# MCU_DAQ.net
KiCad netlist of a schematic drawn in Altium Designer
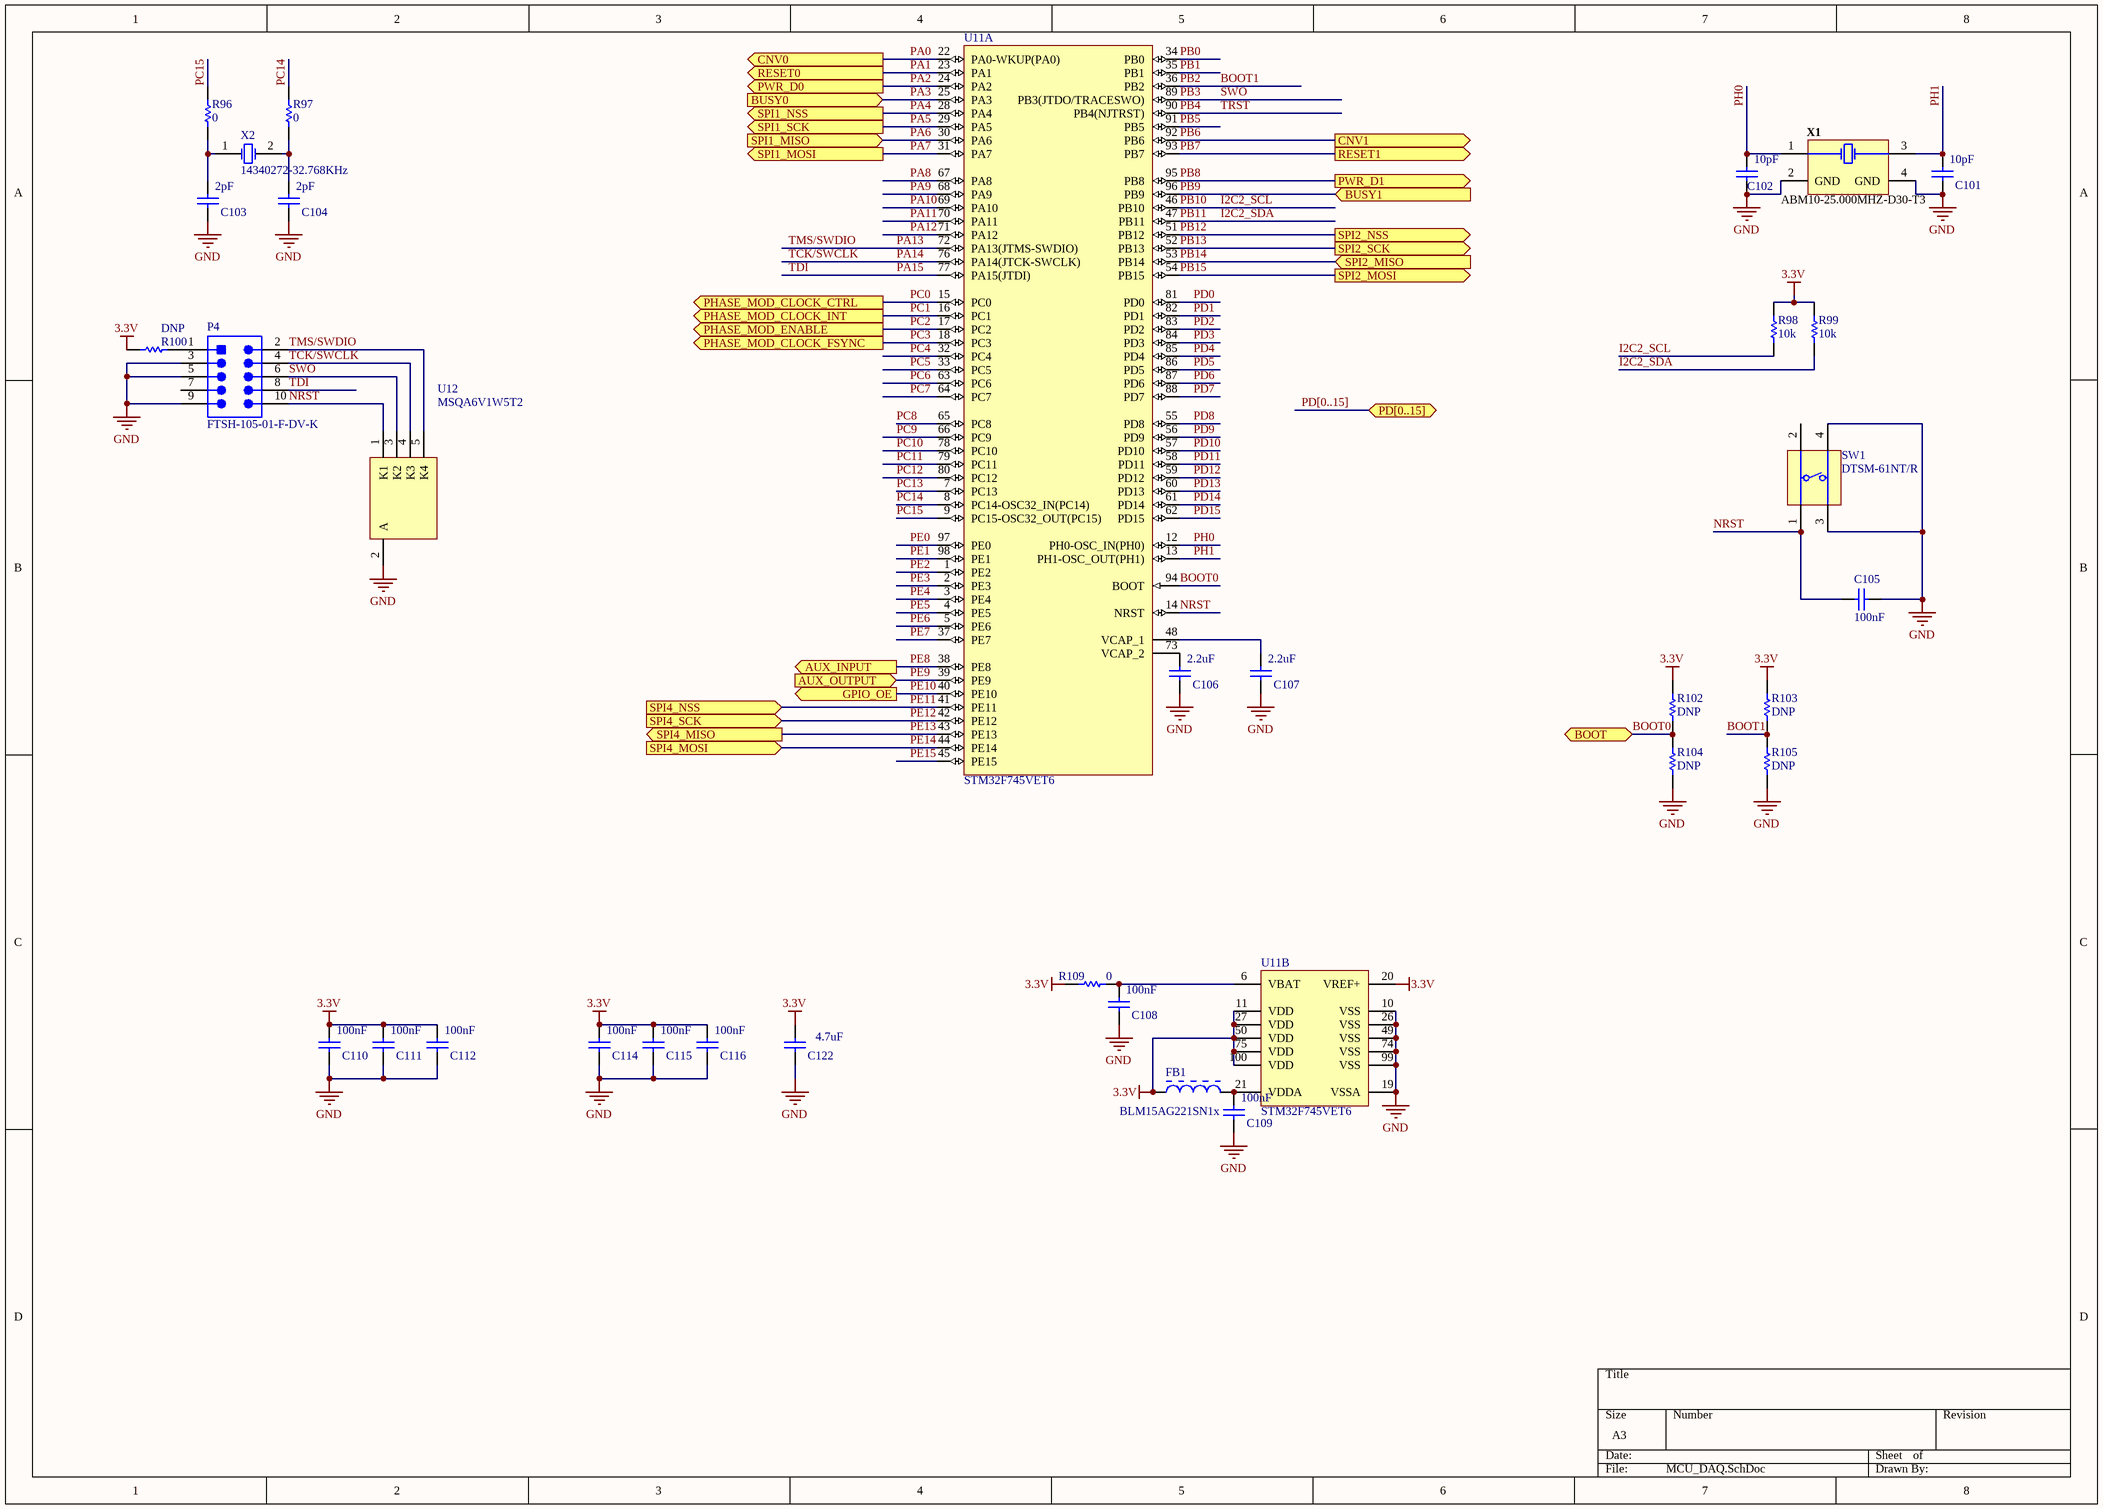
[diagram p0: MCU_DAQ.SchDoc]

(export (version "E")
  (design (tool "Eeschema 10.0.6"))
  (components
    (comp (ref "C101")
      (value "10pF")
      (footprint "CAPC0402(1005)60_L")
      (description "0402 (1005 Metric) Chip Capacitor")
      (fields (field (name "Comment") "CAP0402"))
      (libsource (lib "Altium Content Vault") (part "CMP-1590-00004-1"))
    )
    (comp (ref "C102")
      (value "10pF")
      (footprint "CAPC0402(1005)60_L")
      (description "0402 (1005 Metric) Chip Capacitor")
      (fields (field (name "Comment") "CAP0402"))
      (libsource (lib "Altium Content Vault") (part "CMP-1590-00004-1"))
    )
    (comp (ref "C103")
      (value "2pF")
      (footprint "CAPC0402(1005)60_L")
      (description "0402 (1005 Metric) Chip Capacitor")
      (fields (field (name "Comment") "CAP0402"))
      (libsource (lib "Altium Content Vault") (part "CMP-1590-00004-1"))
    )
    (comp (ref "C104")
      (value "2pF")
      (footprint "CAPC0402(1005)60_L")
      (description "0402 (1005 Metric) Chip Capacitor")
      (fields (field (name "Comment") "CAP0402"))
      (libsource (lib "Altium Content Vault") (part "CMP-1590-00004-1"))
    )
    (comp (ref "C105")
      (value "100nF")
      (footprint "CAPC0402(1005)60_L")
      (description "0402 (1005 Metric) Chip Capacitor")
      (fields (field (name "Comment") "CAP0402"))
      (libsource (lib "Altium Content Vault") (part "CMP-1590-00004-1"))
    )
    (comp (ref "C106")
      (value "2.2uF")
      (footprint "CAPC0402(1005)60_L")
      (description "0402 (1005 Metric) Chip Capacitor")
      (fields (field (name "Comment") "CAP0402"))
      (libsource (lib "Altium Content Vault") (part "CMP-1590-00004-1"))
    )
    (comp (ref "C107")
      (value "2.2uF")
      (footprint "CAPC0402(1005)60_L")
      (description "0402 (1005 Metric) Chip Capacitor")
      (fields (field (name "Comment") "CAP0402"))
      (libsource (lib "Altium Content Vault") (part "CMP-1590-00004-1"))
    )
    (comp (ref "C108")
      (value "100nF")
      (footprint "CAPC0402(1005)60_L")
      (description "0402 (1005 Metric) Chip Capacitor")
      (fields (field (name "Comment") "CAP0402"))
      (libsource (lib "Altium Content Vault") (part "CMP-1590-00004-1"))
    )
    (comp (ref "C109")
      (value "100nF")
      (footprint "CAPC0402(1005)60_L")
      (description "0402 (1005 Metric) Chip Capacitor")
      (fields (field (name "Comment") "CAP0402"))
      (libsource (lib "Altium Content Vault") (part "CMP-1590-00004-1"))
    )
    (comp (ref "C110")
      (value "100nF")
      (footprint "CAPC0402(1005)60_L")
      (description "0402 (1005 Metric) Chip Capacitor")
      (fields (field (name "Comment") "CAP0402"))
      (libsource (lib "Altium Content Vault") (part "CMP-1590-00004-1"))
    )
    (comp (ref "C111")
      (value "100nF")
      (footprint "CAPC0402(1005)60_L")
      (description "0402 (1005 Metric) Chip Capacitor")
      (fields (field (name "Comment") "CAP0402"))
      (libsource (lib "Altium Content Vault") (part "CMP-1590-00004-1"))
    )
    (comp (ref "C112")
      (value "100nF")
      (footprint "CAPC0402(1005)60_L")
      (description "0402 (1005 Metric) Chip Capacitor")
      (fields (field (name "Comment") "CAP0402"))
      (libsource (lib "Altium Content Vault") (part "CMP-1590-00004-1"))
    )
    (comp (ref "C114")
      (value "100nF")
      (footprint "CAPC0402(1005)60_L")
      (description "0402 (1005 Metric) Chip Capacitor")
      (fields (field (name "Comment") "CAP0402"))
      (libsource (lib "Altium Content Vault") (part "CMP-1590-00004-1"))
    )
    (comp (ref "C115")
      (value "100nF")
      (footprint "CAPC0402(1005)60_L")
      (description "0402 (1005 Metric) Chip Capacitor")
      (fields (field (name "Comment") "CAP0402"))
      (libsource (lib "Altium Content Vault") (part "CMP-1590-00004-1"))
    )
    (comp (ref "C116")
      (value "100nF")
      (footprint "CAPC0402(1005)60_L")
      (description "0402 (1005 Metric) Chip Capacitor")
      (fields (field (name "Comment") "CAP0402"))
      (libsource (lib "Altium Content Vault") (part "CMP-1590-00004-1"))
    )
    (comp (ref "C122")
      (value "4.7uF")
      (footprint "CAPC0805(2012)145_L")
      (description "0805 (2012 Metric) Chip Capacitor")
      (fields (field (name "Comment") "CAP0805"))
      (libsource (lib "Altium Content Vault") (part "CMP-1590-00003-1"))
    )
    (comp (ref "FB1")
      (value "BLM15AG221SN1x")
      (footprint "MURA-BLM15AG221SN1x_V")
      (description "Chip Bead, 220 Ohm, +/- 25 %, 100 MHz, 300 mA, -55 to 125 degC, 0402 (1005 Metric), RoHS")
      (fields (field (name "TOLERANCE") "25%"))
      (libsource (lib "Altium Content Vault") (part "BEAD-2"))
    )
    (comp (ref "P4")
      (value "FTSH-105-01-F-DV-K")
      (footprint "SMTC-FTSH-105-01-L-DV-K_V")
      (description "Male Header, Pitch 1.27 mm, 2 x 5 Position, Height 6.12 mm, RoHS, Tube")
      (fields (field (name "MANUFACTURER") "Samtec"))
      (libsource (lib "Altium Content Vault") (part "CN-2P-M-R10"))
    )
    (comp (ref "R96")
      (value "0")
      (footprint "RESC0402(1005)_L")
      (description "0402 (1005 Metric) Chip Resistor")
      (fields (field (name "Comment") "RES0402"))
      (libsource (lib "Altium Content Vault") (part "CMP-1591-00004-1"))
    )
    (comp (ref "R97")
      (value "0")
      (footprint "RESC0402(1005)_L")
      (description "0402 (1005 Metric) Chip Resistor")
      (fields (field (name "Comment") "RES0402"))
      (libsource (lib "Altium Content Vault") (part "CMP-1591-00004-1"))
    )
    (comp (ref "R98")
      (value "10k")
      (footprint "RESC0402(1005)_L")
      (description "0402 (1005 Metric) Chip Resistor")
      (fields (field (name "Comment") "RES0402"))
      (libsource (lib "Altium Content Vault") (part "CMP-1591-00004-1"))
    )
    (comp (ref "R99")
      (value "10k")
      (footprint "RESC0402(1005)_L")
      (description "0402 (1005 Metric) Chip Resistor")
      (fields (field (name "Comment") "RES0402"))
      (libsource (lib "Altium Content Vault") (part "CMP-1591-00004-1"))
    )
    (comp (ref "R100")
      (value "DNP")
      (footprint "RESC0402(1005)_L")
      (description "0402 (1005 Metric) Chip Resistor")
      (fields (field (name "Comment") "RES0402"))
      (libsource (lib "Altium Content Vault") (part "CMP-1591-00004-1"))
    )
    (comp (ref "R102")
      (value "DNP")
      (footprint "RESC0402(1005)_L")
      (description "0402 (1005 Metric) Chip Resistor")
      (fields (field (name "Comment") "RES0402"))
      (libsource (lib "Altium Content Vault") (part "CMP-1591-00004-1"))
    )
    (comp (ref "R103")
      (value "DNP")
      (footprint "RESC0402(1005)_L")
      (description "0402 (1005 Metric) Chip Resistor")
      (fields (field (name "Comment") "RES0402"))
      (libsource (lib "Altium Content Vault") (part "CMP-1591-00004-1"))
    )
    (comp (ref "R104")
      (value "DNP")
      (footprint "RESC0402(1005)_L")
      (description "0402 (1005 Metric) Chip Resistor")
      (fields (field (name "Comment") "RES0402"))
      (libsource (lib "Altium Content Vault") (part "CMP-1591-00004-1"))
    )
    (comp (ref "R105")
      (value "DNP")
      (footprint "RESC0402(1005)_L")
      (description "0402 (1005 Metric) Chip Resistor")
      (fields (field (name "Comment") "RES0402"))
      (libsource (lib "Altium Content Vault") (part "CMP-1591-00004-1"))
    )
    (comp (ref "R109")
      (value "0")
      (footprint "RESC0402(1005)_L")
      (description "0402 (1005 Metric) Chip Resistor")
      (fields (field (name "Comment") "RES0402"))
      (libsource (lib "Altium Content Vault") (part "CMP-1591-00004-1"))
    )
    (comp (ref "SW1")
      (value "DTSM-61NT/R")
      (footprint "DIPT-DTSM-6_V")
      (description "Switch, SPNO Push Button SMD")
      (fields (field (name "MANUFACTURER") "Diptronics"))
      (libsource (lib "Altium Content Vault") (part "DIPT-DTSM-6"))
    )
    (comp (ref "U11")
      (value "STM32F745VET6")
      (footprint "STM-LQFP100_V")
      (fields (field (name "PARTNUMBER") "STM32F745VE"))
      (libsource (lib "Altium Content Vault") (part "STM-STM32F74X-LQFP-100"))
    )
    (comp (ref "U12")
      (value "MSQA6V1W5T2")
      (footprint "ONSC-SC70-5-419A-02_V")
      (description "Quad Array ESD Protection Diodes with Low Clamping Voltage, 5-Pin SC70, Tape and Reel")
      (fields (field (name "MANUFACTURER") "On Semiconductor"))
      (libsource (lib "Altium Content Vault") (part "ONSC-MSQA6V1W5-SC70-5-419A-02"))
    )
    (comp (ref "X1")
      (value "ABM10-25.000MHZ-D30-T3")
      (footprint "ABRA-ABM10_V")
      (fields (field (name "MANUFACTURER") "ABRACON") (field (name "TOLERANCE") "20PPM"))
      (libsource (lib "Altium Content Vault") (part "XTAL-1-3-4"))
    )
    (comp (ref "X2")
      (value "14340272-32.768KHz")
      (footprint "ITTI-14340272-32.768KHz-2_V")
      (description "Crystal, 32.768 KHz, -40 to 85 degC, 3.2 x 1.5 x 0.9 mm SMD")
      (fields (field (name "MANUFACTURER") "ITTI"))
      (libsource (lib "Altium Content Vault") (part "ITTI-14340272-2"))
    )
  )
  (nets
    (net (code "1") (name "/BOOT0") (class "Default")
      (node (ref "R102") (pin "1") (pinfunction "1_1") (pintype "passive"))
      (node (ref "R104") (pin "2") (pinfunction "2_2") (pintype "passive"))
      (node (ref "U11") (pin "94") (pinfunction "BOOT_94") (pintype "input"))
    )
    (net (code "2") (name "/BOOT1") (class "Default")
      (node (ref "R103") (pin "1") (pinfunction "1_1") (pintype "passive"))
      (node (ref "R105") (pin "2") (pinfunction "2_2") (pintype "passive"))
      (node (ref "U11") (pin "36") (pinfunction "PB2_36") (pintype "bidirectional"))
    )
    (net (code "3") (name "/I2C2_SCL") (class "Default")
      (node (ref "R98") (pin "1") (pinfunction "1_1") (pintype "passive"))
      (node (ref "U11") (pin "46") (pinfunction "PB10_46") (pintype "bidirectional"))
    )
    (net (code "4") (name "/I2C2_SDA") (class "Default")
      (node (ref "R99") (pin "1") (pinfunction "1_1") (pintype "passive"))
      (node (ref "U11") (pin "47") (pinfunction "PB11_47") (pintype "bidirectional"))
    )
    (net (code "5") (name "/NRST") (class "Default")
      (node (ref "C105") (pin "1") (pinfunction "1_1") (pintype "passive"))
      (node (ref "P4") (pin "10") (pinfunction "10_10") (pintype "passive"))
      (node (ref "SW1") (pin "1") (pinfunction "T1_1") (pintype "passive"))
      (node (ref "U11") (pin "14") (pinfunction "NRST_14") (pintype "bidirectional"))
      (node (ref "U12") (pin "1") (pinfunction "K1_1") (pintype "passive"))
    )
    (net (code "6") (name "/PA0") (class "Default")
      (node (ref "U11") (pin "22") (pinfunction "PA0-WKUP(PA0)_22") (pintype "bidirectional"))
    )
    (net (code "7") (name "/PA1") (class "Default")
      (node (ref "U11") (pin "23") (pinfunction "PA1_23") (pintype "bidirectional"))
    )
    (net (code "8") (name "/PA2") (class "Default")
      (node (ref "U11") (pin "24") (pinfunction "PA2_24") (pintype "bidirectional"))
    )
    (net (code "9") (name "/PA3") (class "Default")
      (node (ref "U11") (pin "25") (pinfunction "PA3_25") (pintype "bidirectional"))
    )
    (net (code "10") (name "/PA4") (class "Default")
      (node (ref "U11") (pin "28") (pinfunction "PA4_28") (pintype "bidirectional"))
    )
    (net (code "11") (name "/PA5") (class "Default")
      (node (ref "U11") (pin "29") (pinfunction "PA5_29") (pintype "bidirectional"))
    )
    (net (code "12") (name "/PA6") (class "Default")
      (node (ref "U11") (pin "30") (pinfunction "PA6_30") (pintype "bidirectional"))
    )
    (net (code "13") (name "/PA7") (class "Default")
      (node (ref "U11") (pin "31") (pinfunction "PA7_31") (pintype "bidirectional"))
    )
    (net (code "14") (name "/PA8") (class "Default")
      (node (ref "U11") (pin "67") (pinfunction "PA8_67") (pintype "bidirectional"))
    )
    (net (code "15") (name "/PA9") (class "Default")
      (node (ref "U11") (pin "68") (pinfunction "PA9_68") (pintype "bidirectional"))
    )
    (net (code "16") (name "/PA10") (class "Default")
      (node (ref "U11") (pin "69") (pinfunction "PA10_69") (pintype "bidirectional"))
    )
    (net (code "17") (name "/PA11") (class "Default")
      (node (ref "U11") (pin "70") (pinfunction "PA11_70") (pintype "bidirectional"))
    )
    (net (code "18") (name "/PA12") (class "Default")
      (node (ref "U11") (pin "71") (pinfunction "PA12_71") (pintype "bidirectional"))
    )
    (net (code "19") (name "/PA13") (class "Default")
      (node (ref "P4") (pin "2") (pinfunction "2_2") (pintype "passive"))
      (node (ref "U11") (pin "72") (pinfunction "PA13(JTMS-SWDIO)_72") (pintype "bidirectional"))
      (node (ref "U12") (pin "5") (pinfunction "K4_5") (pintype "passive"))
    )
    (net (code "20") (name "/PA14") (class "Default")
      (node (ref "P4") (pin "4") (pinfunction "4_4") (pintype "passive"))
      (node (ref "U11") (pin "76") (pinfunction "PA14(JTCK-SWCLK)_76") (pintype "bidirectional"))
      (node (ref "U12") (pin "4") (pinfunction "K3_4") (pintype "passive"))
    )
    (net (code "21") (name "/PA15") (class "Default")
      (node (ref "P4") (pin "8") (pinfunction "8_8") (pintype "passive"))
      (node (ref "U11") (pin "77") (pinfunction "PA15(JTDI)_77") (pintype "bidirectional"))
    )
    (net (code "22") (name "/PB0") (class "Default")
      (node (ref "U11") (pin "34") (pinfunction "PB0_34") (pintype "bidirectional"))
    )
    (net (code "23") (name "/PB1") (class "Default")
      (node (ref "U11") (pin "35") (pinfunction "PB1_35") (pintype "bidirectional"))
    )
    (net (code "24") (name "/PB3") (class "Default")
      (node (ref "P4") (pin "6") (pinfunction "6_6") (pintype "passive"))
      (node (ref "U11") (pin "89") (pinfunction "PB3(JTDO/TRACESWO)_89") (pintype "bidirectional"))
      (node (ref "U12") (pin "3") (pinfunction "K2_3") (pintype "passive"))
    )
    (net (code "25") (name "/PB4") (class "Default")
      (node (ref "U11") (pin "90") (pinfunction "PB4(NJTRST)_90") (pintype "bidirectional"))
    )
    (net (code "26") (name "/PB5") (class "Default")
      (node (ref "U11") (pin "91") (pinfunction "PB5_91") (pintype "bidirectional"))
    )
    (net (code "27") (name "/PB6") (class "Default")
      (node (ref "U11") (pin "92") (pinfunction "PB6_92") (pintype "bidirectional"))
    )
    (net (code "28") (name "/PB7") (class "Default")
      (node (ref "U11") (pin "93") (pinfunction "PB7_93") (pintype "bidirectional"))
    )
    (net (code "29") (name "/PB8") (class "Default")
      (node (ref "U11") (pin "95") (pinfunction "PB8_95") (pintype "bidirectional"))
    )
    (net (code "30") (name "/PB9") (class "Default")
      (node (ref "U11") (pin "96") (pinfunction "PB9_96") (pintype "bidirectional"))
    )
    (net (code "31") (name "/PB12") (class "Default")
      (node (ref "U11") (pin "51") (pinfunction "PB12_51") (pintype "bidirectional"))
    )
    (net (code "32") (name "/PB13") (class "Default")
      (node (ref "U11") (pin "52") (pinfunction "PB13_52") (pintype "bidirectional"))
    )
    (net (code "33") (name "/PB14") (class "Default")
      (node (ref "U11") (pin "53") (pinfunction "PB14_53") (pintype "bidirectional"))
    )
    (net (code "34") (name "/PB15") (class "Default")
      (node (ref "U11") (pin "54") (pinfunction "PB15_54") (pintype "bidirectional"))
    )
    (net (code "35") (name "/PC0") (class "Default")
      (node (ref "U11") (pin "15") (pinfunction "PC0_15") (pintype "bidirectional"))
    )
    (net (code "36") (name "/PC1") (class "Default")
      (node (ref "U11") (pin "16") (pinfunction "PC1_16") (pintype "bidirectional"))
    )
    (net (code "37") (name "/PC2") (class "Default")
      (node (ref "U11") (pin "17") (pinfunction "PC2_17") (pintype "bidirectional"))
    )
    (net (code "38") (name "/PC3") (class "Default")
      (node (ref "U11") (pin "18") (pinfunction "PC3_18") (pintype "bidirectional"))
    )
    (net (code "39") (name "/PC4") (class "Default")
      (node (ref "U11") (pin "32") (pinfunction "PC4_32") (pintype "bidirectional"))
    )
    (net (code "40") (name "/PC5") (class "Default")
      (node (ref "U11") (pin "33") (pinfunction "PC5_33") (pintype "bidirectional"))
    )
    (net (code "41") (name "/PC6") (class "Default")
      (node (ref "U11") (pin "63") (pinfunction "PC6_63") (pintype "bidirectional"))
    )
    (net (code "42") (name "/PC7") (class "Default")
      (node (ref "U11") (pin "64") (pinfunction "PC7_64") (pintype "bidirectional"))
    )
    (net (code "43") (name "/PC8") (class "Default")
      (node (ref "U11") (pin "65") (pinfunction "PC8_65") (pintype "bidirectional"))
    )
    (net (code "44") (name "/PC9") (class "Default")
      (node (ref "U11") (pin "66") (pinfunction "PC9_66") (pintype "bidirectional"))
    )
    (net (code "45") (name "/PC10") (class "Default")
      (node (ref "U11") (pin "78") (pinfunction "PC10_78") (pintype "bidirectional"))
    )
    (net (code "46") (name "/PC11") (class "Default")
      (node (ref "U11") (pin "79") (pinfunction "PC11_79") (pintype "bidirectional"))
    )
    (net (code "47") (name "/PC12") (class "Default")
      (node (ref "U11") (pin "80") (pinfunction "PC12_80") (pintype "bidirectional"))
    )
    (net (code "48") (name "/PC13") (class "Default")
      (node (ref "U11") (pin "7") (pinfunction "PC13_7") (pintype "bidirectional"))
    )
    (net (code "49") (name "/PC14") (class "Default")
      (node (ref "R97") (pin "1") (pinfunction "1_1") (pintype "passive"))
      (node (ref "U11") (pin "8") (pinfunction "PC14-OSC32_IN(PC14)_8") (pintype "bidirectional"))
    )
    (net (code "50") (name "/PC15") (class "Default")
      (node (ref "R96") (pin "1") (pinfunction "1_1") (pintype "passive"))
      (node (ref "U11") (pin "9") (pinfunction "PC15-OSC32_OUT(PC15)_9") (pintype "bidirectional"))
    )
    (net (code "51") (name "/PD0") (class "Default")
      (node (ref "U11") (pin "81") (pinfunction "PD0_81") (pintype "bidirectional"))
    )
    (net (code "52") (name "/PD1") (class "Default")
      (node (ref "U11") (pin "82") (pinfunction "PD1_82") (pintype "bidirectional"))
    )
    (net (code "53") (name "/PD2") (class "Default")
      (node (ref "U11") (pin "83") (pinfunction "PD2_83") (pintype "bidirectional"))
    )
    (net (code "54") (name "/PD3") (class "Default")
      (node (ref "U11") (pin "84") (pinfunction "PD3_84") (pintype "bidirectional"))
    )
    (net (code "55") (name "/PD4") (class "Default")
      (node (ref "U11") (pin "85") (pinfunction "PD4_85") (pintype "bidirectional"))
    )
    (net (code "56") (name "/PD5") (class "Default")
      (node (ref "U11") (pin "86") (pinfunction "PD5_86") (pintype "bidirectional"))
    )
    (net (code "57") (name "/PD6") (class "Default")
      (node (ref "U11") (pin "87") (pinfunction "PD6_87") (pintype "bidirectional"))
    )
    (net (code "58") (name "/PD7") (class "Default")
      (node (ref "U11") (pin "88") (pinfunction "PD7_88") (pintype "bidirectional"))
    )
    (net (code "59") (name "/PD8") (class "Default")
      (node (ref "U11") (pin "55") (pinfunction "PD8_55") (pintype "bidirectional"))
    )
    (net (code "60") (name "/PD9") (class "Default")
      (node (ref "U11") (pin "56") (pinfunction "PD9_56") (pintype "bidirectional"))
    )
    (net (code "61") (name "/PD10") (class "Default")
      (node (ref "U11") (pin "57") (pinfunction "PD10_57") (pintype "bidirectional"))
    )
    (net (code "62") (name "/PD11") (class "Default")
      (node (ref "U11") (pin "58") (pinfunction "PD11_58") (pintype "bidirectional"))
    )
    (net (code "63") (name "/PD12") (class "Default")
      (node (ref "U11") (pin "59") (pinfunction "PD12_59") (pintype "bidirectional"))
    )
    (net (code "64") (name "/PD13") (class "Default")
      (node (ref "U11") (pin "60") (pinfunction "PD13_60") (pintype "bidirectional"))
    )
    (net (code "65") (name "/PD14") (class "Default")
      (node (ref "U11") (pin "61") (pinfunction "PD14_61") (pintype "bidirectional"))
    )
    (net (code "66") (name "/PD15") (class "Default")
      (node (ref "U11") (pin "62") (pinfunction "PD15_62") (pintype "bidirectional"))
    )
    (net (code "68") (name "/PE0") (class "Default")
      (node (ref "U11") (pin "97") (pinfunction "PE0_97") (pintype "bidirectional"))
    )
    (net (code "69") (name "/PE1") (class "Default")
      (node (ref "U11") (pin "98") (pinfunction "PE1_98") (pintype "bidirectional"))
    )
    (net (code "70") (name "/PE2") (class "Default")
      (node (ref "U11") (pin "1") (pinfunction "PE2_1") (pintype "bidirectional"))
    )
    (net (code "71") (name "/PE3") (class "Default")
      (node (ref "U11") (pin "2") (pinfunction "PE3_2") (pintype "bidirectional"))
    )
    (net (code "72") (name "/PE4") (class "Default")
      (node (ref "U11") (pin "3") (pinfunction "PE4_3") (pintype "bidirectional"))
    )
    (net (code "73") (name "/PE5") (class "Default")
      (node (ref "U11") (pin "4") (pinfunction "PE5_4") (pintype "bidirectional"))
    )
    (net (code "74") (name "/PE6") (class "Default")
      (node (ref "U11") (pin "5") (pinfunction "PE6_5") (pintype "bidirectional"))
    )
    (net (code "75") (name "/PE7") (class "Default")
      (node (ref "U11") (pin "37") (pinfunction "PE7_37") (pintype "bidirectional"))
    )
    (net (code "76") (name "/PE8") (class "Default")
      (node (ref "U11") (pin "38") (pinfunction "PE8_38") (pintype "bidirectional"))
    )
    (net (code "77") (name "/PE9") (class "Default")
      (node (ref "U11") (pin "39") (pinfunction "PE9_39") (pintype "bidirectional"))
    )
    (net (code "78") (name "/PE10") (class "Default")
      (node (ref "U11") (pin "40") (pinfunction "PE10_40") (pintype "bidirectional"))
    )
    (net (code "79") (name "/PE11") (class "Default")
      (node (ref "U11") (pin "41") (pinfunction "PE11_41") (pintype "bidirectional"))
    )
    (net (code "80") (name "/PE12") (class "Default")
      (node (ref "U11") (pin "42") (pinfunction "PE12_42") (pintype "bidirectional"))
    )
    (net (code "81") (name "/PE13") (class "Default")
      (node (ref "U11") (pin "43") (pinfunction "PE13_43") (pintype "bidirectional"))
    )
    (net (code "82") (name "/PE14") (class "Default")
      (node (ref "U11") (pin "44") (pinfunction "PE14_44") (pintype "bidirectional"))
    )
    (net (code "83") (name "/PE15") (class "Default")
      (node (ref "U11") (pin "45") (pinfunction "PE15_45") (pintype "bidirectional"))
    )
    (net (code "84") (name "/PH0") (class "Default")
      (node (ref "C102") (pin "1") (pinfunction "1_1") (pintype "passive"))
      (node (ref "U11") (pin "12") (pinfunction "PH0-OSC_IN(PH0)_12") (pintype "bidirectional"))
      (node (ref "X1") (pin "1") (pinfunction "X1_1") (pintype "passive"))
    )
    (net (code "85") (name "/PH1") (class "Default")
      (node (ref "C101") (pin "1") (pinfunction "1_1") (pintype "passive"))
      (node (ref "U11") (pin "13") (pinfunction "PH1-OSC_OUT(PH1)_13") (pintype "bidirectional"))
      (node (ref "X1") (pin "3") (pinfunction "X2_3") (pintype "passive"))
    )
    (net (code "86") (name "3.3V") (class "Default")
      (node (ref "C110") (pin "1") (pinfunction "1_1") (pintype "passive"))
      (node (ref "C111") (pin "1") (pinfunction "1_1") (pintype "passive"))
      (node (ref "C112") (pin "1") (pinfunction "1_1") (pintype "passive"))
      (node (ref "C114") (pin "1") (pinfunction "1_1") (pintype "passive"))
      (node (ref "C115") (pin "1") (pinfunction "1_1") (pintype "passive"))
      (node (ref "C116") (pin "1") (pinfunction "1_1") (pintype "passive"))
      (node (ref "C122") (pin "2") (pinfunction "2_2") (pintype "passive"))
      (node (ref "FB1") (pin "1") (pinfunction "1_1") (pintype "passive"))
      (node (ref "R100") (pin "2") (pinfunction "2_2") (pintype "passive"))
      (node (ref "R102") (pin "2") (pinfunction "2_2") (pintype "passive"))
      (node (ref "R103") (pin "2") (pinfunction "2_2") (pintype "passive"))
      (node (ref "R109") (pin "2") (pinfunction "2_2") (pintype "passive"))
      (node (ref "R98") (pin "2") (pinfunction "2_2") (pintype "passive"))
      (node (ref "R99") (pin "2") (pinfunction "2_2") (pintype "passive"))
      (node (ref "U11") (pin "100") (pinfunction "VDD_100") (pintype "power_in"))
      (node (ref "U11") (pin "11") (pinfunction "VDD_11") (pintype "power_in"))
      (node (ref "U11") (pin "20") (pinfunction "VREF+_20") (pintype "power_in"))
      (node (ref "U11") (pin "27") (pinfunction "VDD_27") (pintype "power_in"))
      (node (ref "U11") (pin "50") (pinfunction "VDD_50") (pintype "power_in"))
      (node (ref "U11") (pin "75") (pinfunction "VDD_75") (pintype "power_in"))
    )
    (net (code "87") (name "GND") (class "Default")
      (node (ref "C101") (pin "2") (pinfunction "2_2") (pintype "passive"))
      (node (ref "C102") (pin "2") (pinfunction "2_2") (pintype "passive"))
      (node (ref "C103") (pin "2") (pinfunction "2_2") (pintype "passive"))
      (node (ref "C104") (pin "2") (pinfunction "2_2") (pintype "passive"))
      (node (ref "C105") (pin "2") (pinfunction "2_2") (pintype "passive"))
      (node (ref "C106") (pin "2") (pinfunction "2_2") (pintype "passive"))
      (node (ref "C107") (pin "2") (pinfunction "2_2") (pintype "passive"))
      (node (ref "C108") (pin "2") (pinfunction "2_2") (pintype "passive"))
      (node (ref "C109") (pin "2") (pinfunction "2_2") (pintype "passive"))
      (node (ref "C110") (pin "2") (pinfunction "2_2") (pintype "passive"))
      (node (ref "C111") (pin "2") (pinfunction "2_2") (pintype "passive"))
      (node (ref "C112") (pin "2") (pinfunction "2_2") (pintype "passive"))
      (node (ref "C114") (pin "2") (pinfunction "2_2") (pintype "passive"))
      (node (ref "C115") (pin "2") (pinfunction "2_2") (pintype "passive"))
      (node (ref "C116") (pin "2") (pinfunction "2_2") (pintype "passive"))
      (node (ref "C122") (pin "1") (pinfunction "1_1") (pintype "passive"))
      (node (ref "P4") (pin "3") (pinfunction "3_3") (pintype "passive"))
      (node (ref "P4") (pin "5") (pinfunction "5_5") (pintype "passive"))
      (node (ref "P4") (pin "9") (pinfunction "9_9") (pintype "passive"))
      (node (ref "R104") (pin "1") (pinfunction "1_1") (pintype "passive"))
      (node (ref "R105") (pin "1") (pinfunction "1_1") (pintype "passive"))
      (node (ref "SW1") (pin "3") (pinfunction "T3_3") (pintype "passive"))
      (node (ref "SW1") (pin "4") (pinfunction "T3_4") (pintype "passive"))
      (node (ref "U11") (pin "10") (pinfunction "VSS_10") (pintype "power_in"))
      (node (ref "U11") (pin "19") (pinfunction "VSSA_19") (pintype "power_in"))
      (node (ref "U11") (pin "26") (pinfunction "VSS_26") (pintype "power_in"))
      (node (ref "U11") (pin "49") (pinfunction "VSS_49") (pintype "power_in"))
      (node (ref "U11") (pin "74") (pinfunction "VSS_74") (pintype "power_in"))
      (node (ref "U11") (pin "99") (pinfunction "VSS_99") (pintype "power_in"))
      (node (ref "U12") (pin "2") (pinfunction "A_2") (pintype "passive"))
      (node (ref "X1") (pin "2") (pinfunction "GND_2") (pintype "power_in"))
      (node (ref "X1") (pin "4") (pinfunction "GND_4") (pintype "power_in"))
    )
    (net (code "88") (name "Net-(P4-Pad1)") (class "Default")
      (node (ref "P4") (pin "1") (pinfunction "1_1") (pintype "passive"))
      (node (ref "R100") (pin "1") (pinfunction "1_1") (pintype "passive"))
    )
    (net (code "89") (name "Net-(U11A-VCAP_1)") (class "Default")
      (node (ref "C107") (pin "1") (pinfunction "1_1") (pintype "passive"))
      (node (ref "U11") (pin "48") (pinfunction "VCAP_1_48") (pintype "power_in"))
    )
    (net (code "90") (name "Net-(U11A-VCAP_2)") (class "Default")
      (node (ref "C106") (pin "1") (pinfunction "1_1") (pintype "passive"))
      (node (ref "U11") (pin "73") (pinfunction "VCAP_2_73") (pintype "power_in"))
    )
    (net (code "91") (name "Net-(U11B-VBAT)") (class "Default")
      (node (ref "C108") (pin "1") (pinfunction "1_1") (pintype "passive"))
      (node (ref "R109") (pin "1") (pinfunction "1_1") (pintype "passive"))
      (node (ref "U11") (pin "6") (pinfunction "VBAT_6") (pintype "power_in"))
    )
    (net (code "92") (name "Net-(U11B-VDDA)") (class "Default")
      (node (ref "C109") (pin "1") (pinfunction "1_1") (pintype "passive"))
      (node (ref "FB1") (pin "2") (pinfunction "2_2") (pintype "passive"))
      (node (ref "U11") (pin "21") (pinfunction "VDDA_21") (pintype "power_in"))
    )
    (net (code "93") (name "Net-(X2-X1)") (class "Default")
      (node (ref "C103") (pin "1") (pinfunction "1_1") (pintype "passive"))
      (node (ref "R96") (pin "2") (pinfunction "2_2") (pintype "passive"))
      (node (ref "X2") (pin "1") (pinfunction "X1_1") (pintype "passive"))
    )
    (net (code "94") (name "Net-(X2-X2)") (class "Default")
      (node (ref "C104") (pin "1") (pinfunction "1_1") (pintype "passive"))
      (node (ref "R97") (pin "2") (pinfunction "2_2") (pintype "passive"))
      (node (ref "X2") (pin "2") (pinfunction "X2_2") (pintype "passive"))
    )
    (net (code "95") (name "unconnected-(P4-Pad7)") (class "Default")
      (node (ref "P4") (pin "7") (pinfunction "7_7") (pintype "passive"))
    )
    (net (code "96") (name "unconnected-(SW1-T2-Pad2)") (class "Default")
      (node (ref "SW1") (pin "2") (pinfunction "T2_2") (pintype "passive"))
    )
  )
)
